# Sheet6.net
KiCad netlist of a schematic drawn in Altium Designer
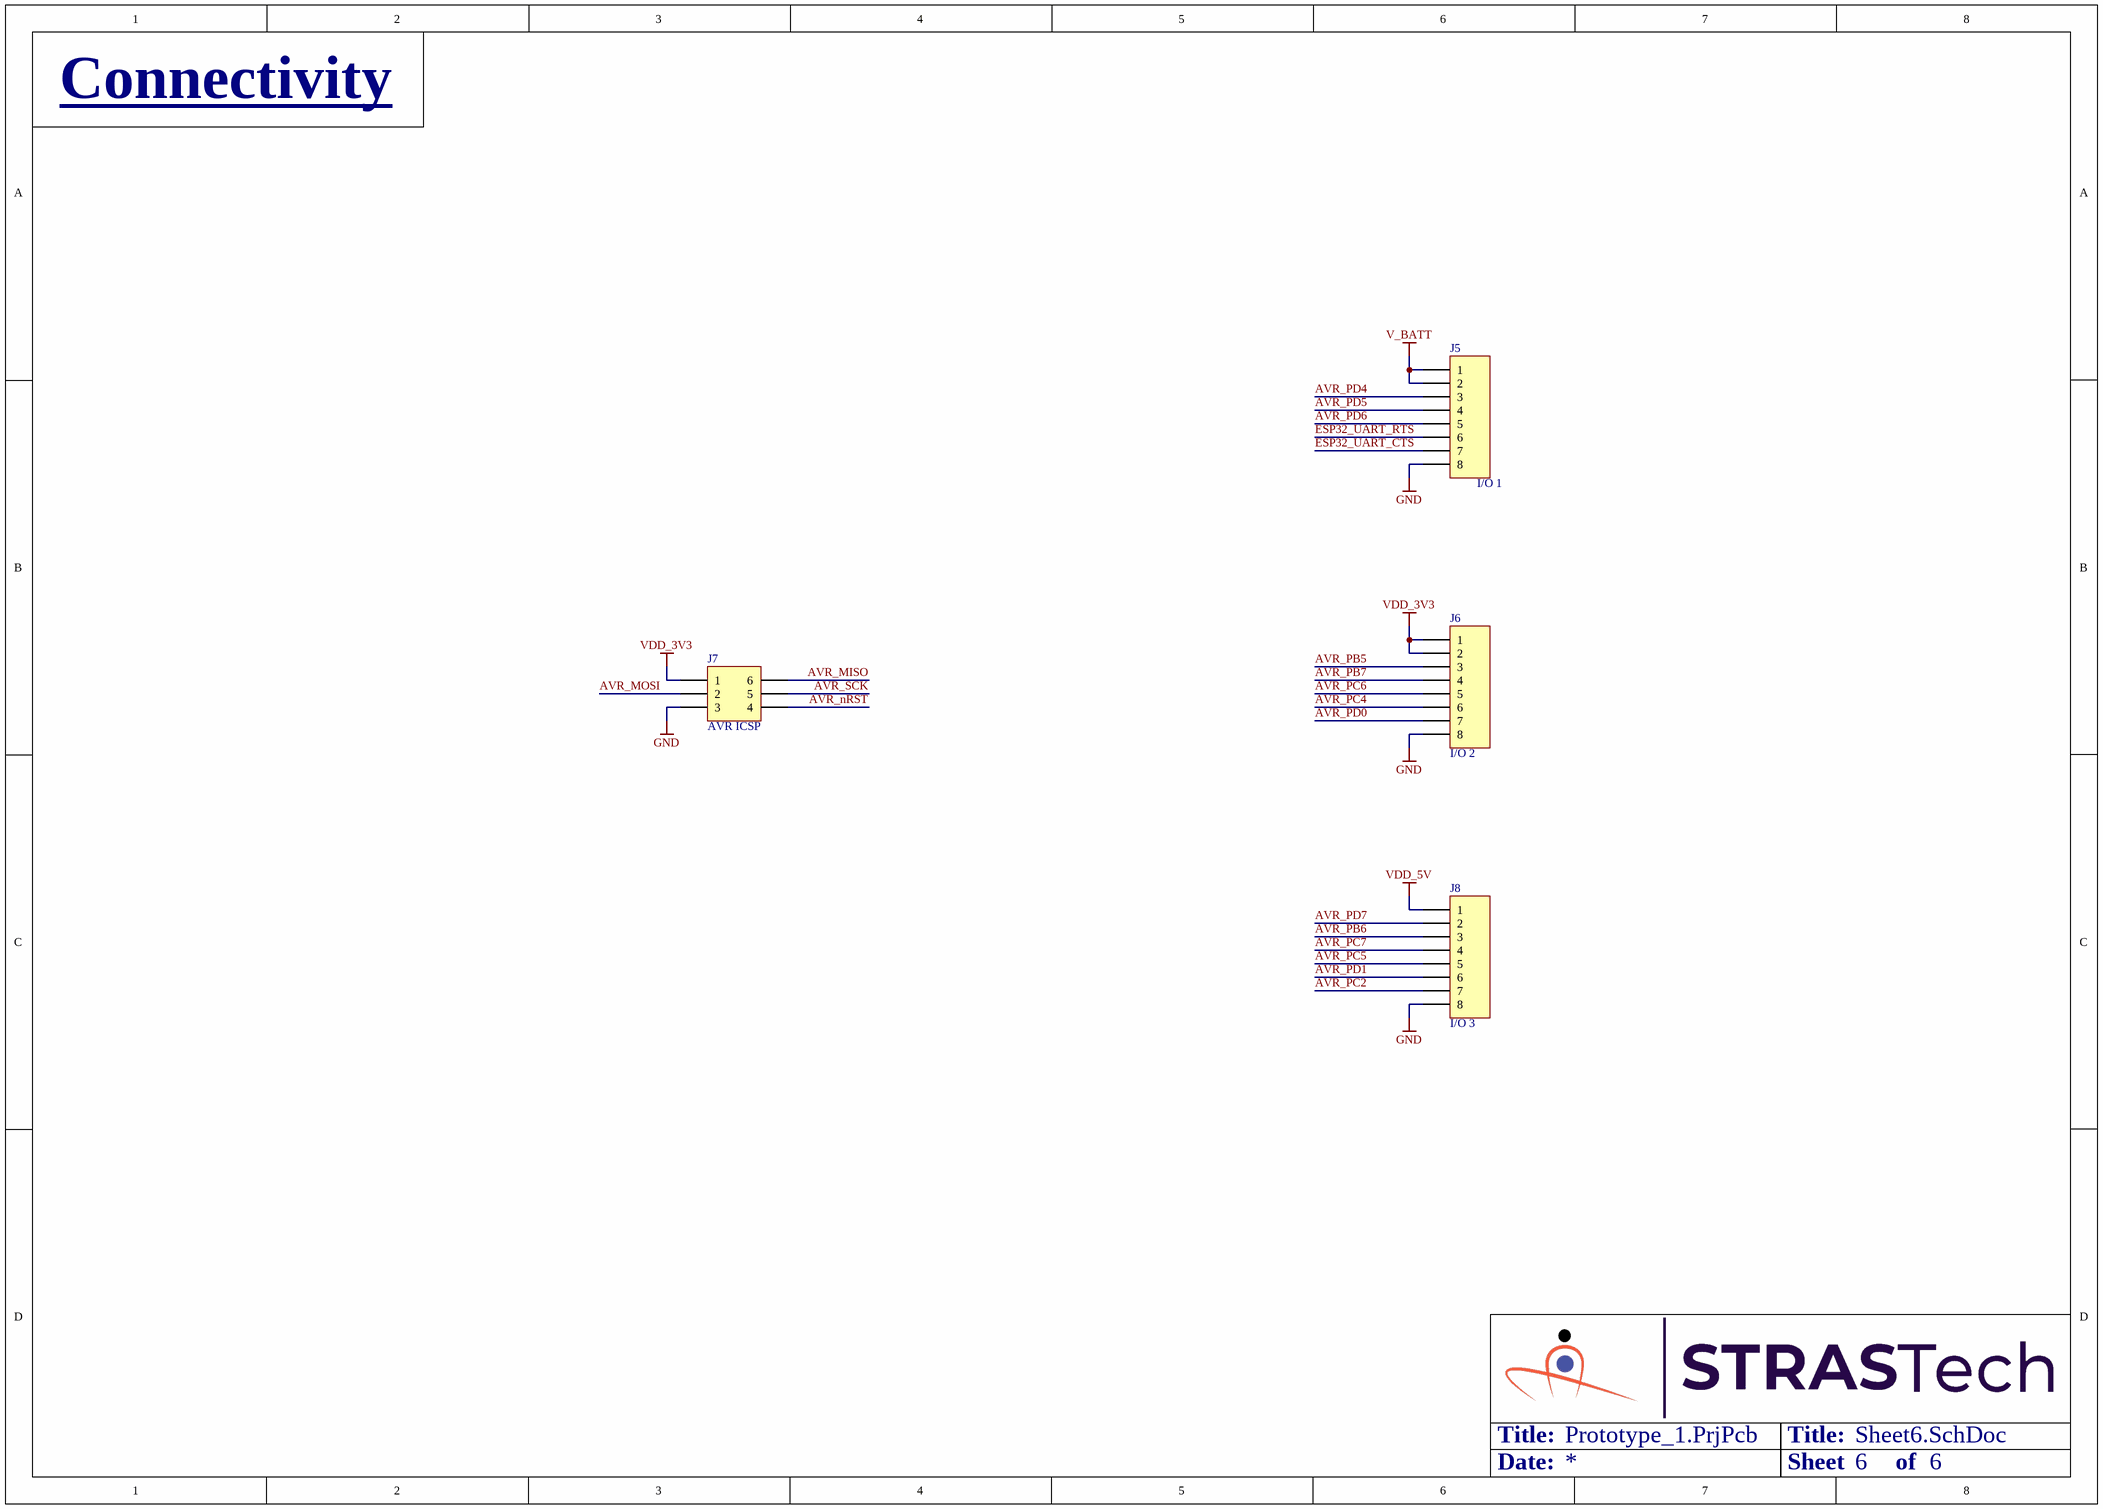
[diagram p0: Sheet6.SchDoc]

(export (version "E")
  (design (tool "Eeschema 10.0.6"))
  (components
    (comp (ref "J5")
      (value "Term,Header,8 Pin,Top,2.54mm")
      (footprint "Term,Header,8Pin,2.54mm")
      (description "CONN HEADER VERT 8POS 2.54MM")
      (fields
        (field (name "VENDOR PART NUMBER") "732-5321-ND")
        (field (name "MANUFACTURER") "Würth Elektronik")
        (field (name "CREATED BY") "Judd Foster")
      )
      (libsource (lib "symbols") (part "Term,Header,8 Pin,Top,2.54mm"))
    )
    (comp (ref "J6")
      (value "Term,Header,8 Pin,Top,2.54mm")
      (footprint "Term,Header,8Pin,2.54mm")
      (description "CONN HEADER VERT 8POS 2.54MM")
      (fields
        (field (name "VENDOR PART NUMBER") "732-5321-ND")
        (field (name "MANUFACTURER") "Würth Elektronik")
        (field (name "CREATED BY") "Judd Foster")
      )
      (libsource (lib "symbols") (part "Term,Header,8 Pin,Top,2.54mm"))
    )
    (comp (ref "J7")
      (value "Term,Header,3x2 Pin,2.54mm,SMD")
      (footprint "TERM,HEADER,3X2PIN,P2.54,SMD")
      (description "Connector Header Surface Mount 6 position 0.100\" (2.54mm)")
      (fields
        (field (name "VENDOR PART NUMBER") "609-10129383-906002ALFCT-ND")
        (field (name "MANUFACTURER") "Amphenol ICC (FCI)")
        (field (name "CREATEDBY") "Judd Foster")
      )
      (libsource (lib "symbols") (part "Term,Header,3x2 Pin,2.54mm,SMD"))
    )
    (comp (ref "J8")
      (value "Term,Header,8 Pin,Top,2.54mm")
      (footprint "Term,Header,8Pin,2.54mm")
      (description "CONN HEADER VERT 8POS 2.54MM")
      (fields
        (field (name "VENDOR PART NUMBER") "732-5321-ND")
        (field (name "MANUFACTURER") "Würth Elektronik")
        (field (name "CREATED BY") "Judd Foster")
      )
      (libsource (lib "symbols") (part "Term,Header,8 Pin,Top,2.54mm"))
    )
  )
  (nets
    (net (code "1") (name "/AVR_MISO") (class "Default")
      (node (ref "J7") (pin "6") (pinfunction "6_6") (pintype "passive"))
    )
    (net (code "2") (name "/AVR_MOSI") (class "Default")
      (node (ref "J7") (pin "2") (pinfunction "2_2") (pintype "passive"))
    )
    (net (code "3") (name "/AVR_PB5") (class "Default")
      (node (ref "J6") (pin "3") (pinfunction "3_3") (pintype "passive"))
    )
    (net (code "4") (name "/AVR_PB6") (class "Default")
      (node (ref "J8") (pin "3") (pinfunction "3_3") (pintype "passive"))
    )
    (net (code "5") (name "/AVR_PB7") (class "Default")
      (node (ref "J6") (pin "4") (pinfunction "4_4") (pintype "passive"))
    )
    (net (code "6") (name "/AVR_PC2") (class "Default")
      (node (ref "J8") (pin "7") (pinfunction "7_7") (pintype "passive"))
    )
    (net (code "7") (name "/AVR_PC4") (class "Default")
      (node (ref "J6") (pin "6") (pinfunction "6_6") (pintype "passive"))
    )
    (net (code "8") (name "/AVR_PC5") (class "Default")
      (node (ref "J8") (pin "5") (pinfunction "5_5") (pintype "passive"))
    )
    (net (code "9") (name "/AVR_PC6") (class "Default")
      (node (ref "J6") (pin "5") (pinfunction "5_5") (pintype "passive"))
    )
    (net (code "10") (name "/AVR_PC7") (class "Default")
      (node (ref "J8") (pin "4") (pinfunction "4_4") (pintype "passive"))
    )
    (net (code "11") (name "/AVR_PD0") (class "Default")
      (node (ref "J6") (pin "7") (pinfunction "7_7") (pintype "passive"))
    )
    (net (code "12") (name "/AVR_PD1") (class "Default")
      (node (ref "J8") (pin "6") (pinfunction "6_6") (pintype "passive"))
    )
    (net (code "13") (name "/AVR_PD4") (class "Default")
      (node (ref "J5") (pin "3") (pinfunction "3_3") (pintype "passive"))
    )
    (net (code "14") (name "/AVR_PD5") (class "Default")
      (node (ref "J5") (pin "4") (pinfunction "4_4") (pintype "passive"))
    )
    (net (code "15") (name "/AVR_PD6") (class "Default")
      (node (ref "J5") (pin "5") (pinfunction "5_5") (pintype "passive"))
    )
    (net (code "16") (name "/AVR_PD7") (class "Default")
      (node (ref "J8") (pin "2") (pinfunction "2_2") (pintype "passive"))
    )
    (net (code "17") (name "/AVR_SCK") (class "Default")
      (node (ref "J7") (pin "5") (pinfunction "5_5") (pintype "passive"))
    )
    (net (code "18") (name "/AVR_nRST") (class "Default")
      (node (ref "J7") (pin "4") (pinfunction "4_4") (pintype "passive"))
    )
    (net (code "19") (name "/ESP32_UART_CTS") (class "Default")
      (node (ref "J5") (pin "7") (pinfunction "7_7") (pintype "passive"))
    )
    (net (code "20") (name "/ESP32_UART_RTS") (class "Default")
      (node (ref "J5") (pin "6") (pinfunction "6_6") (pintype "passive"))
    )
    (net (code "21") (name "GND") (class "Default")
      (node (ref "J5") (pin "8") (pinfunction "8_8") (pintype "passive"))
      (node (ref "J6") (pin "8") (pinfunction "8_8") (pintype "passive"))
      (node (ref "J7") (pin "3") (pinfunction "3_3") (pintype "passive"))
      (node (ref "J8") (pin "8") (pinfunction "8_8") (pintype "passive"))
    )
    (net (code "22") (name "VDD_3V3") (class "Default")
      (node (ref "J6") (pin "1") (pinfunction "1_1") (pintype "passive"))
      (node (ref "J6") (pin "2") (pinfunction "2_2") (pintype "passive"))
      (node (ref "J7") (pin "1") (pinfunction "1_1") (pintype "passive"))
    )
    (net (code "23") (name "VDD_5V") (class "Default")
      (node (ref "J8") (pin "1") (pinfunction "1_1") (pintype "passive"))
    )
    (net (code "24") (name "V_BATT") (class "Default")
      (node (ref "J5") (pin "1") (pinfunction "1_1") (pintype "passive"))
      (node (ref "J5") (pin "2") (pinfunction "2_2") (pintype "passive"))
    )
  )
)
